# TopLevel.net
KiCad netlist of a schematic drawn in Altium Designer
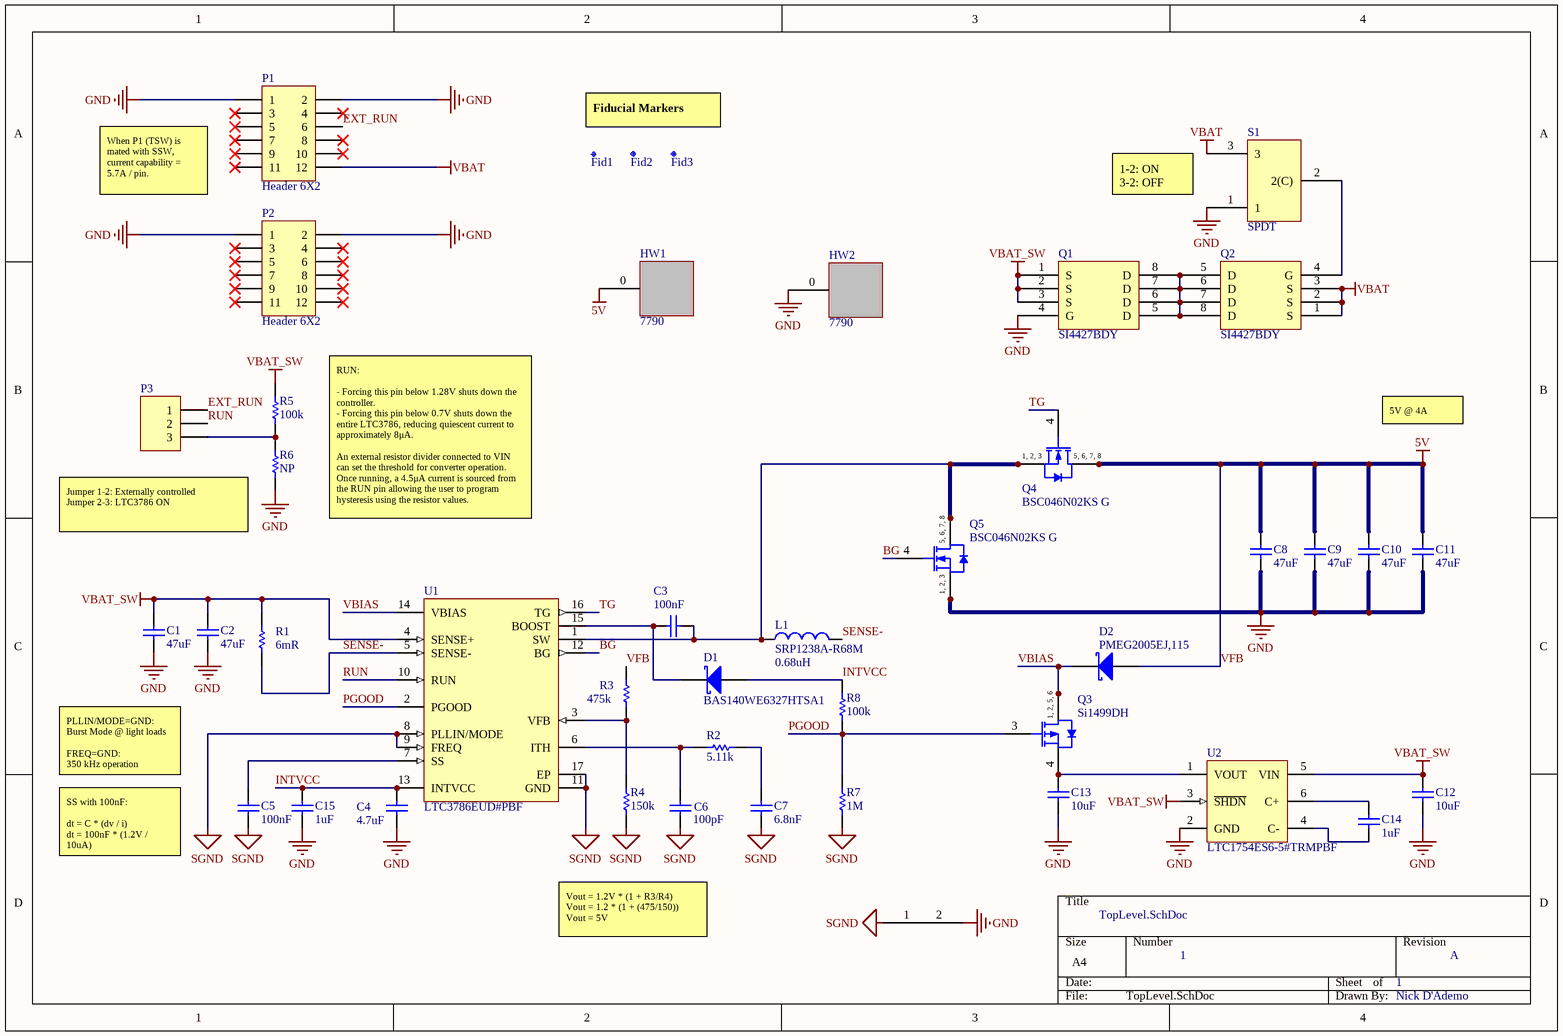
[diagram p0: TopLevel.SchDoc]

(export (version "E")
  (design (tool "Eeschema 10.0.6"))
  (components
    (comp (ref "C1")
      (value "47uF")
      (footprint "CAPC3225N")
      (description "MURATA - GRM32ER71A476KE15L - CAP CER 47UF 10V X7R 1210")
      (fields (field (name "Comment") "Cap") (field (name "PUBLISHER") "Altium Limited"))
      (libsource (lib "Miscellaneous Devices") (part "Cap"))
    )
    (comp (ref "C2")
      (value "47uF")
      (footprint "CAPC3225N")
      (description "MURATA - GRM32ER71A476KE15L - CAP CER 47UF 10V X7R 1210")
      (fields (field (name "Comment") "Cap") (field (name "PUBLISHER") "Altium Limited"))
      (libsource (lib "Miscellaneous Devices") (part "Cap"))
    )
    (comp (ref "C3")
      (value "100nF")
      (footprint "CAPC1005N")
      (description "TDK - C1005X7R1C104K050BC - CAP CER 0.1UF 16V X7R 0402")
      (fields (field (name "Comment") "Cap") (field (name "PUBLISHER") "Altium Limited"))
      (libsource (lib "Miscellaneous Devices") (part "Cap"))
    )
    (comp (ref "C4")
      (value "4.7uF")
      (footprint "CAPC1005N")
      (description "TDK - C1005X5R1A475K050BC - CAP CER 4.7UF 10V X5R 0402")
      (fields (field (name "Comment") "Cap") (field (name "PUBLISHER") "Altium Limited"))
      (libsource (lib "Miscellaneous Devices") (part "Cap"))
    )
    (comp (ref "C5")
      (value "100nF")
      (footprint "CAPC1005N")
      (description "TDK - C1005X7R1C104K050BC - CAP CER 0.1UF 16V X7R 0402")
      (fields (field (name "Comment") "Cap") (field (name "PUBLISHER") "Altium Limited"))
      (libsource (lib "Miscellaneous Devices") (part "Cap"))
    )
    (comp (ref "C6")
      (value "100pF")
      (footprint "CAPC1005N")
      (description "KEMET - C0402C101J5GACTU -  CAP CER 100PF 50V NP0 0402")
      (fields (field (name "Comment") "Cap") (field (name "PUBLISHER") "Altium Limited"))
      (libsource (lib "Miscellaneous Devices") (part "Cap"))
    )
    (comp (ref "C7")
      (value "6.8nF")
      (footprint "CAPC1005N")
      (description "MURATA - GRM155R71E682KA01D - CAP CER 6800PF 25V X7R 0402")
      (fields (field (name "Comment") "Cap") (field (name "PUBLISHER") "Altium Limited"))
      (libsource (lib "Miscellaneous Devices") (part "Cap"))
    )
    (comp (ref "C8")
      (value "47uF")
      (footprint "CAPC3225N")
      (description "MURATA - GRM32ER71A476KE15L - CAP CER 47UF 10V X7R 1210")
      (fields (field (name "Comment") "Cap") (field (name "PUBLISHER") "Altium Limited"))
      (libsource (lib "Miscellaneous Devices") (part "Cap"))
    )
    (comp (ref "C9")
      (value "47uF")
      (footprint "CAPC3225N")
      (description "MURATA - GRM32ER71A476KE15L - CAP CER 47UF 10V X7R 1210")
      (fields (field (name "Comment") "Cap") (field (name "PUBLISHER") "Altium Limited"))
      (libsource (lib "Miscellaneous Devices") (part "Cap"))
    )
    (comp (ref "C10")
      (value "47uF")
      (footprint "CAPC3225N")
      (description "MURATA - GRM32ER71A476KE15L - CAP CER 47UF 10V X7R 1210")
      (fields (field (name "Comment") "Cap") (field (name "PUBLISHER") "Altium Limited"))
      (libsource (lib "Miscellaneous Devices") (part "Cap"))
    )
    (comp (ref "C11")
      (value "47uF")
      (footprint "CAPC3225N")
      (description "MURATA - GRM32ER71A476KE15L - CAP CER 47UF 10V X7R 1210")
      (fields (field (name "Comment") "Cap") (field (name "PUBLISHER") "Altium Limited"))
      (libsource (lib "Miscellaneous Devices") (part "Cap"))
    )
    (comp (ref "C12")
      (value "10uF")
      (footprint "CAPC1005N")
      (description "TDK - C1005X5R0J106M050BC - CAP CER 10UF 6.3V X5R 0402")
      (fields (field (name "Comment") "Cap") (field (name "PUBLISHER") "Altium Limited"))
      (libsource (lib "Miscellaneous Devices") (part "Cap"))
    )
    (comp (ref "C13")
      (value "10uF")
      (footprint "CAPC1005N")
      (description "TDK - C1005X5R0J106M050BC - CAP CER 10UF 6.3V X5R 0402")
      (fields (field (name "Comment") "Cap") (field (name "PUBLISHER") "Altium Limited"))
      (libsource (lib "Miscellaneous Devices") (part "Cap"))
    )
    (comp (ref "C14")
      (value "1uF")
      (footprint "CAPC1005N")
      (description "MURATA - GRM155R61A105KE15D - CAP CER 1UF 10V X5R 0402")
      (fields (field (name "Comment") "Cap") (field (name "PUBLISHER") "Altium Limited"))
      (libsource (lib "Miscellaneous Devices") (part "Cap"))
    )
    (comp (ref "C15")
      (value "1uF")
      (footprint "CAPC1005N")
      (description "MURATA - GRM155R61A105KE15D - CAP CER 1UF 10V X5R 0402")
      (fields (field (name "Comment") "Cap") (field (name "PUBLISHER") "Altium Limited"))
      (libsource (lib "Miscellaneous Devices") (part "Cap"))
    )
    (comp (ref "D1")
      (value "BAS140WE6327HTSA1")
      (footprint "SOD323")
      (description "INFINEON TECHNOLOGIES - BAS140WE6327HTSA1 - DIODE SCHOTTKY 40V 120MA SOD323")
      (fields (field (name "PUBLISHER") "Altium Limited"))
      (libsource (lib "Miscellaneous Devices") (part "D Schottky"))
    )
    (comp (ref "D2")
      (value "PMEG2005EJ,115")
      (footprint "SOD323F")
      (description "NXP SEMICONDUCTORS - PMEG2005EJ,115 - DIODE SCHOTTKY 20V 500MA SOD323F")
      (fields (field (name "PUBLISHER") "Altium Limited"))
      (libsource (lib "Miscellaneous Devices") (part "D Schottky"))
    )
    (comp (ref "Fid1")
      (value "Fiducial mark")
      (footprint "Fiducial_BOTTOM")
      (description "Fiducial Mark")
      (fields (field (name "PART NUMBER") "Fid-Mark") (field (name "PUBLISHER") "Nordic Semiconductor"))
      (libsource (lib "pca10004") (part "Fiducial"))
    )
    (comp (ref "Fid2")
      (value "Fiducial mark")
      (footprint "Fiducial_BOTTOM")
      (description "Fiducial Mark")
      (fields (field (name "PART NUMBER") "Fid-Mark") (field (name "PUBLISHER") "Nordic Semiconductor"))
      (libsource (lib "pca10004") (part "Fiducial"))
    )
    (comp (ref "Fid3")
      (value "Fiducial mark")
      (footprint "Fiducial_BOTTOM")
      (description "Fiducial Mark")
      (fields (field (name "PART NUMBER") "Fid-Mark") (field (name "PUBLISHER") "Nordic Semiconductor"))
      (libsource (lib "pca10004") (part "Fiducial"))
    )
    (comp (ref "HW1")
      (value "7790")
      (footprint "7790")
      (description "KEYSTONE ELECTRONICS - 7790 - TERM PCB SNAP-IN HORZ M3 THREAD")
      (libsource (lib "eBug2014-Parallella-Carrier-H") (part "7790"))
    )
    (comp (ref "HW2")
      (value "7790")
      (footprint "7790")
      (description "KEYSTONE ELECTRONICS - 7790 - TERM PCB SNAP-IN HORZ M3 THREAD")
      (libsource (lib "eBug2014-Parallella-Carrier-H") (part "7790"))
    )
    (comp (ref "L1")
      (value "SRP1238A-R68M")
      (footprint "SRP1238A")
      (description "BOURNS INC - SRP1238A-R68M - FIXED IND 680NH 28A 2.5 MOHM SMD")
      (fields (field (name "ALTIUM_VALUE") "0.68uH") (field (name "PUBLISHER") "Altium Limited"))
      (libsource (lib "Miscellaneous Devices") (part "Inductor"))
    )
    (comp (ref "NT1")
      (value "NETTIE1")
      (footprint "NETTIE1")
      (libsource (lib "eBug2014-Parallella-Carrier-H") (part "NETTIE1"))
    )
    (comp (ref "P1")
      (value "Header 6X2")
      (footprint "TSW-106-05-G-D")
      (fields (field (name "PUBLISHER") "Altium Limited"))
      (libsource (lib "Miscellaneous Connectors") (part "Header 6X2"))
    )
    (comp (ref "P2")
      (value "Header 6X2")
      (footprint "TSW-106-05-G-D")
      (fields (field (name "PUBLISHER") "Altium Limited"))
      (libsource (lib "Miscellaneous Connectors") (part "Header 6X2"))
    )
    (comp (ref "P3")
      (value "~")
      (footprint "TSW-103-05-T-S")
      (fields (field (name "PUBLISHER") "Altium Limited"))
      (libsource (lib "Miscellaneous Connectors") (part "Header 3"))
    )
    (comp (ref "Q1")
      (value "SI4427BDY")
      (footprint "SOIC127P600-8AN")
      (description "VISHAY SILICONIX - SI4427BDY-T1-E3 - MOSFET P-CH 30V 9.7A 8-SOIC")
      (libsource (lib "eBug2014") (part "SI4427BDY"))
    )
    (comp (ref "Q2")
      (value "SI4427BDY")
      (footprint "SOIC127P600-8AN")
      (description "VISHAY SILICONIX - SI4427BDY-T1-E3 - MOSFET P-CH 30V 9.7A 8-SOIC")
      (libsource (lib "") (part "SI4427BDY_1"))
    )
    (comp (ref "Q3")
      (value "Si1499DH")
      (footprint "SOT363-6N")
      (description "VISHAY SILICONIX - SI1499DH-T1-E3 - MOSFET P-CH 8V 1.6A SC70-6")
      (fields (field (name "PUBLISHER") "Altium Limited"))
      (libsource (lib "eBug2014-Parallella-Carrier-H") (part "Si1499DH"))
    )
    (comp (ref "Q4")
      (value "BSC046N02KS G")
      (footprint "INF-PG-TDSON-8-1_V")
      (fields (field (name "MANUFACTURER") "Infineon"))
      (libsource (lib "Infineon Power MOSFET") (part "BSC046N02KS G"))
    )
    (comp (ref "Q5")
      (value "BSC046N02KS G")
      (footprint "INF-PG-TDSON-8-1_V")
      (fields (field (name "MANUFACTURER") "Infineon"))
      (libsource (lib "Infineon Power MOSFET") (part "BSC046N02KS G"))
    )
    (comp (ref "R1")
      (value "6mR")
      (footprint "RESC2012N")
      (description "VISHAY DALE - WSLP08056L000FEA18 - RES SMD 0.006 OHM 1% 1W 0805")
      (fields (field (name "Comment") "Res1") (field (name "PUBLISHER") "Altium Limited"))
      (libsource (lib "Miscellaneous Devices") (part "Res1"))
    )
    (comp (ref "R2")
      (value "5.11k")
      (footprint "RESC1005N")
      (description "PANASONIC - ERJ-2RKF5111X - RES SMD 5.11K OHM 1% 1/10W 0402")
      (fields (field (name "Comment") "Res1") (field (name "PUBLISHER") "Altium Limited"))
      (libsource (lib "Miscellaneous Devices") (part "Res1"))
    )
    (comp (ref "R3")
      (value "475k")
      (footprint "RESC1005N")
      (description "PANASONIC - ERJ-2RKF4753X - RES SMD 475K OHM 1% 1/10W 0402")
      (fields (field (name "Comment") "Res1") (field (name "PUBLISHER") "Altium Limited"))
      (libsource (lib "Miscellaneous Devices") (part "Res1"))
    )
    (comp (ref "R4")
      (value "150k")
      (footprint "RESC1005N")
      (description "PANASONIC - ERJ-2RKF1503X - RES SMD 150K OHM 1% 1/10W 0402")
      (fields (field (name "Comment") "Res1") (field (name "PUBLISHER") "Altium Limited"))
      (libsource (lib "Miscellaneous Devices") (part "Res1"))
    )
    (comp (ref "R5")
      (value "100k")
      (footprint "RESC1005N")
      (description "PANASONIC - ERJ-2RKF1003X - RES SMD 100K OHM 1% 1/10W 0402")
      (fields (field (name "Comment") "Res1") (field (name "PUBLISHER") "Altium Limited"))
      (libsource (lib "Miscellaneous Devices") (part "Res1"))
    )
    (comp (ref "R6")
      (value "NP")
      (footprint "RESC1005N")
      (description "Resistor")
      (fields (field (name "Comment") "Res1") (field (name "PUBLISHER") "Altium Limited"))
      (libsource (lib "Miscellaneous Devices") (part "Res1"))
    )
    (comp (ref "R7")
      (value "1M")
      (footprint "RESC1005N")
      (description "PANASONIC - ERJ-2RKF1004X - RES SMD 1M OHM 1% 1/10W 0402")
      (fields (field (name "Comment") "Res1") (field (name "PUBLISHER") "Altium Limited"))
      (libsource (lib "Miscellaneous Devices") (part "Res1"))
    )
    (comp (ref "R8")
      (value "100k")
      (footprint "RESC1005N")
      (description "PANASONIC - ERJ-2RKF1003X - RES SMD 100K OHM 1% 1/10W 0402")
      (fields (field (name "Comment") "Res1") (field (name "PUBLISHER") "Altium Limited"))
      (libsource (lib "Miscellaneous Devices") (part "Res1"))
    )
    (comp (ref "S1")
      (value "SPDT")
      (footprint "CL-SB-12B-11T")
      (description "COPAL ELECTRONICS INC - CL-SB-12B-11T - SWITCH SLIDE SPDT 200MA 12V")
      (libsource (lib "eBug2014-Parallella-Carrier-H") (part "CL-SB-12B-01T"))
    )
    (comp (ref "U1")
      (value "LTC3786EUD#PBF")
      (footprint "LT-UD-16_N")
      (fields (field (name "MANUFACTURER") "Linear Technology"))
      (libsource (lib "Linear Technology Power Management Switching Regulator LTC1174-LTC3901") (part "LTC3786EUD#PBF"))
    )
    (comp (ref "U2")
      (value "LTC1754ES6-5#TRMPBF")
      (footprint "LT-S6-6-SOT-23_N")
      (fields (field (name "MANUFACTURER") "Linear Technology"))
      (libsource (lib "Linear Technology Power Management Inductorless (Charge Pump) DC-DC Converters") (part "LTC1754ES6-5#TRMPBF"))
    )
  )
  (nets
    (net (code "1") (name "/BG") (class "Default")
      (node (ref "Q5") (pin "4") (pinfunction "GATE_4") (pintype "passive"))
      (node (ref "U1") (pin "12") (pinfunction "BG_12") (pintype "output"))
    )
    (net (code "2") (name "/EXT_RUN") (class "Default")
      (node (ref "P1") (pin "6") (pinfunction "6_6") (pintype "passive"))
      (node (ref "P3") (pin "1") (pinfunction "1_1") (pintype "passive"))
    )
    (net (code "3") (name "/INTVCC") (class "Default")
      (node (ref "C15") (pin "1") (pinfunction "1_1") (pintype "passive"))
      (node (ref "C4") (pin "1") (pinfunction "1_1") (pintype "passive"))
      (node (ref "D1") (pin "1") (pinfunction "A_1") (pintype "passive"))
      (node (ref "R8") (pin "1") (pinfunction "1_1") (pintype "passive"))
      (node (ref "U1") (pin "13") (pinfunction "INTVCC_13") (pintype "power_in"))
    )
    (net (code "4") (name "/PGOOD") (class "Default")
      (node (ref "Q3") (pin "3") (pinfunction "G_3") (pintype "passive"))
      (node (ref "R7") (pin "1") (pinfunction "1_1") (pintype "passive"))
      (node (ref "R8") (pin "2") (pinfunction "2_2") (pintype "passive"))
      (node (ref "U1") (pin "2") (pinfunction "PGOOD_2") (pintype "open_collector"))
    )
    (net (code "5") (name "/RUN") (class "Default")
      (node (ref "P3") (pin "2") (pinfunction "2_2") (pintype "passive"))
      (node (ref "U1") (pin "10") (pinfunction "RUN_10") (pintype "input"))
    )
    (net (code "6") (name "/SENSE-") (class "Default")
      (node (ref "L1") (pin "2") (pinfunction "2_2") (pintype "passive"))
      (node (ref "R1") (pin "1") (pinfunction "1_1") (pintype "passive"))
      (node (ref "U1") (pin "5") (pinfunction "SENSE-_5") (pintype "input"))
    )
    (net (code "7") (name "/TG") (class "Default")
      (node (ref "Q4") (pin "4") (pinfunction "GATE_4") (pintype "passive"))
      (node (ref "U1") (pin "16") (pinfunction "TG_16") (pintype "output"))
    )
    (net (code "8") (name "/VBIAS") (class "Default")
      (node (ref "D2") (pin "2") (pinfunction "K_2") (pintype "passive"))
      (node (ref "Q3") (pin "1") (pinfunction "D_1") (pintype "passive"))
      (node (ref "Q3") (pin "2") (pinfunction "D_2") (pintype "passive"))
      (node (ref "Q3") (pin "5") (pinfunction "D_5") (pintype "passive"))
      (node (ref "Q3") (pin "6") (pinfunction "D_6") (pintype "passive"))
      (node (ref "U1") (pin "14") (pinfunction "VBIAS_14") (pintype "power_in"))
    )
    (net (code "9") (name "5V") (class "Default")
      (node (ref "C10") (pin "1") (pinfunction "1_1") (pintype "passive"))
      (node (ref "C11") (pin "1") (pinfunction "1_1") (pintype "passive"))
      (node (ref "C8") (pin "1") (pinfunction "1_1") (pintype "passive"))
      (node (ref "C9") (pin "1") (pinfunction "1_1") (pintype "passive"))
      (node (ref "D2") (pin "1") (pinfunction "A_1") (pintype "passive"))
      (node (ref "HW1") (pin "0") (pintype "passive"))
      (node (ref "Q4") (pin "5") (pinfunction "DRAIN_5") (pintype "passive"))
      (node (ref "Q4") (pin "6") (pinfunction "DRAIN_6") (pintype "passive"))
      (node (ref "Q4") (pin "7") (pinfunction "DRAIN_7") (pintype "passive"))
      (node (ref "Q4") (pin "8") (pinfunction "DRAIN_8") (pintype "passive"))
      (node (ref "R3") (pin "1") (pinfunction "1_1") (pintype "passive"))
    )
    (net (code "10") (name "GND") (class "Default")
      (node (ref "C1") (pin "2") (pinfunction "2_2") (pintype "passive"))
      (node (ref "C10") (pin "2") (pinfunction "2_2") (pintype "passive"))
      (node (ref "C11") (pin "2") (pinfunction "2_2") (pintype "passive"))
      (node (ref "C12") (pin "2") (pinfunction "2_2") (pintype "passive"))
      (node (ref "C13") (pin "2") (pinfunction "2_2") (pintype "passive"))
      (node (ref "C15") (pin "2") (pinfunction "2_2") (pintype "passive"))
      (node (ref "C2") (pin "2") (pinfunction "2_2") (pintype "passive"))
      (node (ref "C4") (pin "2") (pinfunction "2_2") (pintype "passive"))
      (node (ref "C8") (pin "2") (pinfunction "2_2") (pintype "passive"))
      (node (ref "C9") (pin "2") (pinfunction "2_2") (pintype "passive"))
      (node (ref "HW2") (pin "0") (pintype "passive"))
      (node (ref "NT1") (pin "2") (pinfunction "2_2") (pintype "passive"))
      (node (ref "P1") (pin "1") (pinfunction "1_1") (pintype "passive"))
      (node (ref "P1") (pin "2") (pinfunction "2_2") (pintype "passive"))
      (node (ref "P2") (pin "1") (pinfunction "1_1") (pintype "passive"))
      (node (ref "P2") (pin "2") (pinfunction "2_2") (pintype "passive"))
      (node (ref "Q1") (pin "4") (pinfunction "G_4") (pintype "passive"))
      (node (ref "Q5") (pin "1") (pinfunction "SOURCE_1") (pintype "passive"))
      (node (ref "Q5") (pin "2") (pinfunction "SOURCE_2") (pintype "passive"))
      (node (ref "Q5") (pin "3") (pinfunction "SOURCE_3") (pintype "passive"))
      (node (ref "R6") (pin "2") (pinfunction "2_2") (pintype "passive"))
      (node (ref "S1") (pin "1") (pinfunction "1_1") (pintype "passive"))
      (node (ref "U2") (pin "2") (pinfunction "GND_2") (pintype "power_in"))
    )
    (net (code "11") (name "Net-(C7-Pad1)") (class "Default")
      (node (ref "C7") (pin "1") (pinfunction "1_1") (pintype "passive"))
      (node (ref "R2") (pin "1") (pinfunction "1_1") (pintype "passive"))
    )
    (net (code "12") (name "Net-(D1-K)") (class "Default")
      (node (ref "C3") (pin "2") (pinfunction "2_2") (pintype "passive"))
      (node (ref "D1") (pin "2") (pinfunction "K_2") (pintype "passive"))
      (node (ref "U1") (pin "15") (pinfunction "BOOST_15") (pintype "passive"))
    )
    (net (code "13") (name "Net-(P3-Pad3)") (class "Default")
      (node (ref "P3") (pin "3") (pinfunction "3_3") (pintype "passive"))
      (node (ref "R5") (pin "2") (pinfunction "2_2") (pintype "passive"))
      (node (ref "R6") (pin "1") (pinfunction "1_1") (pintype "passive"))
    )
    (net (code "14") (name "Net-(Q1-D-Pad5)") (class "Default")
      (node (ref "Q1") (pin "5") (pinfunction "D_5") (pintype "passive"))
      (node (ref "Q1") (pin "6") (pinfunction "D_6") (pintype "passive"))
      (node (ref "Q1") (pin "7") (pinfunction "D_7") (pintype "passive"))
      (node (ref "Q1") (pin "8") (pinfunction "D_8") (pintype "passive"))
      (node (ref "Q2") (pin "5") (pinfunction "D_5") (pintype "passive"))
      (node (ref "Q2") (pin "6") (pinfunction "D_6") (pintype "passive"))
      (node (ref "Q2") (pin "7") (pinfunction "D_7") (pintype "passive"))
      (node (ref "Q2") (pin "8") (pinfunction "D_8") (pintype "passive"))
    )
    (net (code "15") (name "Net-(Q2-G)") (class "Default")
      (node (ref "Q2") (pin "4") (pinfunction "G_4") (pintype "passive"))
      (node (ref "S1") (pin "2") (pinfunction "2(C)_2") (pintype "passive"))
    )
    (net (code "16") (name "Net-(Q3-S)") (class "Default")
      (node (ref "C13") (pin "1") (pinfunction "1_1") (pintype "passive"))
      (node (ref "Q3") (pin "4") (pinfunction "S_4") (pintype "passive"))
      (node (ref "U2") (pin "1") (pinfunction "VOUT_1") (pintype "power_in"))
    )
    (net (code "17") (name "Net-(U1-ITH)") (class "Default")
      (node (ref "C6") (pin "1") (pinfunction "1_1") (pintype "passive"))
      (node (ref "R2") (pin "2") (pinfunction "2_2") (pintype "passive"))
      (node (ref "U1") (pin "6") (pinfunction "ITH_6") (pintype "passive"))
    )
    (net (code "18") (name "Net-(U1-SS)") (class "Default")
      (node (ref "C5") (pin "2") (pinfunction "2_2") (pintype "passive"))
      (node (ref "U1") (pin "7") (pinfunction "SS_7") (pintype "input"))
    )
    (net (code "19") (name "Net-(U1-SW)") (class "Default")
      (node (ref "C3") (pin "1") (pinfunction "1_1") (pintype "passive"))
      (node (ref "L1") (pin "1") (pinfunction "1_1") (pintype "passive"))
      (node (ref "Q4") (pin "1") (pinfunction "SOURCE_1") (pintype "passive"))
      (node (ref "Q4") (pin "2") (pinfunction "SOURCE_2") (pintype "passive"))
      (node (ref "Q4") (pin "3") (pinfunction "SOURCE_3") (pintype "passive"))
      (node (ref "Q5") (pin "5") (pinfunction "DRAIN_5") (pintype "passive"))
      (node (ref "Q5") (pin "6") (pinfunction "DRAIN_6") (pintype "passive"))
      (node (ref "Q5") (pin "7") (pinfunction "DRAIN_7") (pintype "passive"))
      (node (ref "Q5") (pin "8") (pinfunction "DRAIN_8") (pintype "passive"))
      (node (ref "U1") (pin "1") (pinfunction "SW_1") (pintype "passive"))
    )
    (net (code "20") (name "Net-(U1-VFB)") (class "Default")
      (node (ref "R3") (pin "2") (pinfunction "2_2") (pintype "passive"))
      (node (ref "R4") (pin "1") (pinfunction "1_1") (pintype "passive"))
      (node (ref "U1") (pin "3") (pinfunction "VFB_3") (pintype "input"))
    )
    (net (code "21") (name "Net-(U2-C+)") (class "Default")
      (node (ref "C14") (pin "1") (pinfunction "1_1") (pintype "passive"))
      (node (ref "U2") (pin "6") (pinfunction "C+_6") (pintype "passive"))
    )
    (net (code "22") (name "Net-(U2-C-)") (class "Default")
      (node (ref "C14") (pin "2") (pinfunction "2_2") (pintype "passive"))
      (node (ref "U2") (pin "4") (pinfunction "C-_4") (pintype "passive"))
    )
    (net (code "23") (name "SGND") (class "Default")
      (node (ref "C5") (pin "1") (pinfunction "1_1") (pintype "passive"))
      (node (ref "C6") (pin "2") (pinfunction "2_2") (pintype "passive"))
      (node (ref "C7") (pin "2") (pinfunction "2_2") (pintype "passive"))
      (node (ref "NT1") (pin "1") (pinfunction "1_1") (pintype "passive"))
      (node (ref "R4") (pin "2") (pinfunction "2_2") (pintype "passive"))
      (node (ref "R7") (pin "2") (pinfunction "2_2") (pintype "passive"))
      (node (ref "U1") (pin "11") (pinfunction "GND_11") (pintype "power_in"))
      (node (ref "U1") (pin "17") (pinfunction "EP_17") (pintype "power_in"))
      (node (ref "U1") (pin "8") (pinfunction "PLLIN/MODE_8") (pintype "input"))
      (node (ref "U1") (pin "9") (pinfunction "FREQ_9") (pintype "input"))
    )
    (net (code "24") (name "VBAT") (class "Default")
      (node (ref "P1") (pin "12") (pinfunction "12_12") (pintype "passive"))
      (node (ref "Q2") (pin "1") (pinfunction "S_1") (pintype "passive"))
      (node (ref "Q2") (pin "2") (pinfunction "S_2") (pintype "passive"))
      (node (ref "Q2") (pin "3") (pinfunction "S_3") (pintype "passive"))
      (node (ref "S1") (pin "3") (pinfunction "3_3") (pintype "passive"))
    )
    (net (code "25") (name "VBAT_SW") (class "Default")
      (node (ref "C1") (pin "1") (pinfunction "1_1") (pintype "passive"))
      (node (ref "C12") (pin "1") (pinfunction "1_1") (pintype "passive"))
      (node (ref "C2") (pin "1") (pinfunction "1_1") (pintype "passive"))
      (node (ref "Q1") (pin "1") (pinfunction "S_1") (pintype "passive"))
      (node (ref "Q1") (pin "2") (pinfunction "S_2") (pintype "passive"))
      (node (ref "Q1") (pin "3") (pinfunction "S_3") (pintype "passive"))
      (node (ref "R1") (pin "2") (pinfunction "2_2") (pintype "passive"))
      (node (ref "R5") (pin "1") (pinfunction "1_1") (pintype "passive"))
      (node (ref "U1") (pin "4") (pinfunction "SENSE+_4") (pintype "input"))
      (node (ref "U2") (pin "3") (pinfunction "~{SHDN}_3") (pintype "input"))
      (node (ref "U2") (pin "5") (pinfunction "VIN_5") (pintype "power_in"))
    )
    (net (code "26") (name "unconnected-(P1-Pad3)") (class "Default")
      (node (ref "P1") (pin "3") (pinfunction "3_3") (pintype "passive+no_connect"))
    )
    (net (code "27") (name "unconnected-(P1-Pad4)") (class "Default")
      (node (ref "P1") (pin "4") (pinfunction "4_4") (pintype "passive+no_connect"))
    )
    (net (code "28") (name "unconnected-(P1-Pad5)") (class "Default")
      (node (ref "P1") (pin "5") (pinfunction "5_5") (pintype "passive+no_connect"))
    )
    (net (code "29") (name "unconnected-(P1-Pad7)") (class "Default")
      (node (ref "P1") (pin "7") (pinfunction "7_7") (pintype "passive+no_connect"))
    )
    (net (code "30") (name "unconnected-(P1-Pad8)") (class "Default")
      (node (ref "P1") (pin "8") (pinfunction "8_8") (pintype "passive+no_connect"))
    )
    (net (code "31") (name "unconnected-(P1-Pad9)") (class "Default")
      (node (ref "P1") (pin "9") (pinfunction "9_9") (pintype "passive+no_connect"))
    )
    (net (code "32") (name "unconnected-(P1-Pad10)") (class "Default")
      (node (ref "P1") (pin "10") (pinfunction "10_10") (pintype "passive+no_connect"))
    )
    (net (code "33") (name "unconnected-(P1-Pad11)") (class "Default")
      (node (ref "P1") (pin "11") (pinfunction "11_11") (pintype "passive+no_connect"))
    )
    (net (code "34") (name "unconnected-(P2-Pad3)") (class "Default")
      (node (ref "P2") (pin "3") (pinfunction "3_3") (pintype "passive+no_connect"))
    )
    (net (code "35") (name "unconnected-(P2-Pad4)") (class "Default")
      (node (ref "P2") (pin "4") (pinfunction "4_4") (pintype "passive+no_connect"))
    )
    (net (code "36") (name "unconnected-(P2-Pad5)") (class "Default")
      (node (ref "P2") (pin "5") (pinfunction "5_5") (pintype "passive+no_connect"))
    )
    (net (code "37") (name "unconnected-(P2-Pad6)") (class "Default")
      (node (ref "P2") (pin "6") (pinfunction "6_6") (pintype "passive+no_connect"))
    )
    (net (code "38") (name "unconnected-(P2-Pad7)") (class "Default")
      (node (ref "P2") (pin "7") (pinfunction "7_7") (pintype "passive+no_connect"))
    )
    (net (code "39") (name "unconnected-(P2-Pad8)") (class "Default")
      (node (ref "P2") (pin "8") (pinfunction "8_8") (pintype "passive+no_connect"))
    )
    (net (code "40") (name "unconnected-(P2-Pad9)") (class "Default")
      (node (ref "P2") (pin "9") (pinfunction "9_9") (pintype "passive+no_connect"))
    )
    (net (code "41") (name "unconnected-(P2-Pad10)") (class "Default")
      (node (ref "P2") (pin "10") (pinfunction "10_10") (pintype "passive+no_connect"))
    )
    (net (code "42") (name "unconnected-(P2-Pad11)") (class "Default")
      (node (ref "P2") (pin "11") (pinfunction "11_11") (pintype "passive+no_connect"))
    )
    (net (code "43") (name "unconnected-(P2-Pad12)") (class "Default")
      (node (ref "P2") (pin "12") (pinfunction "12_12") (pintype "passive+no_connect"))
    )
  )
)
